# expansion_module_dual_rotary_encoder.net
KiCad netlist of a schematic drawn in EAGLE
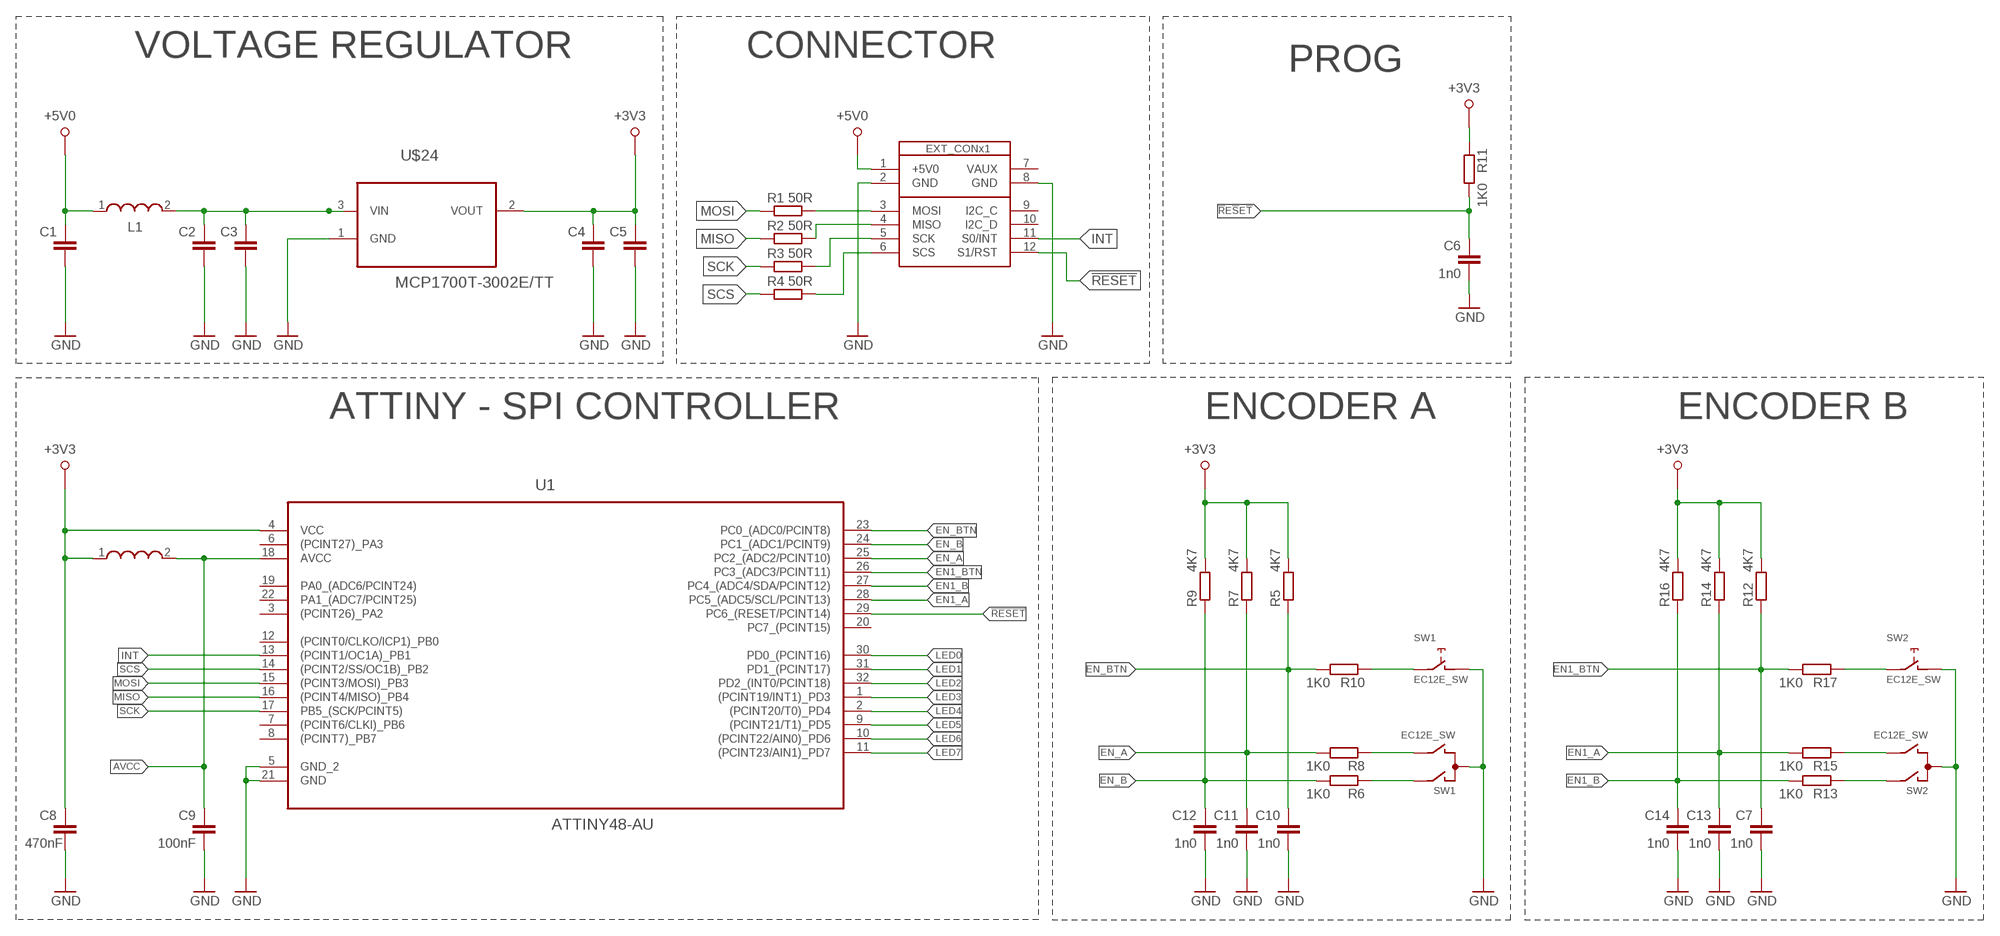
[diagram p0: schematic, sheet 1]

(export (version "E")
  (design (tool "Eeschema 10.0.6"))
  (components
    (comp (ref "C1")
      (value "C-EUC0805")
      (footprint "eagle-import:C0805")
      (libsource (lib "eagle-import") (part "C-EUC0805"))
    )
    (comp (ref "C2")
      (value "C-EUC0805")
      (footprint "eagle-import:C0805")
      (libsource (lib "eagle-import") (part "C-EUC0805"))
    )
    (comp (ref "C3")
      (value "C-EUC0805")
      (footprint "eagle-import:C0805")
      (libsource (lib "eagle-import") (part "C-EUC0805"))
    )
    (comp (ref "C4")
      (value "C-EUC0805")
      (footprint "eagle-import:C0805")
      (libsource (lib "eagle-import") (part "C-EUC0805"))
    )
    (comp (ref "C5")
      (value "C-EUC0805")
      (footprint "eagle-import:C0805")
      (libsource (lib "eagle-import") (part "C-EUC0805"))
    )
    (comp (ref "C6")
      (value "1n0")
      (footprint "eagle-import:C0805")
      (libsource (lib "eagle-import") (part "C-EUC0805"))
    )
    (comp (ref "C7")
      (value "1n0")
      (footprint "eagle-import:C0805")
      (libsource (lib "eagle-import") (part "C-EUC0805"))
    )
    (comp (ref "C8")
      (value "470nF")
      (footprint "eagle-import:C0805")
      (libsource (lib "eagle-import") (part "C-EUC0805"))
    )
    (comp (ref "C9")
      (value "100nF")
      (footprint "eagle-import:C0805")
      (libsource (lib "eagle-import") (part "C-EUC0805"))
    )
    (comp (ref "C10")
      (value "1n0")
      (footprint "eagle-import:C0805")
      (libsource (lib "eagle-import") (part "C-EUC0805"))
    )
    (comp (ref "C11")
      (value "1n0")
      (footprint "eagle-import:C0805")
      (libsource (lib "eagle-import") (part "C-EUC0805"))
    )
    (comp (ref "C12")
      (value "1n0")
      (footprint "eagle-import:C0805")
      (libsource (lib "eagle-import") (part "C-EUC0805"))
    )
    (comp (ref "C13")
      (value "1n0")
      (footprint "eagle-import:C0805")
      (libsource (lib "eagle-import") (part "C-EUC0805"))
    )
    (comp (ref "C14")
      (value "1n0")
      (footprint "eagle-import:C0805")
      (libsource (lib "eagle-import") (part "C-EUC0805"))
    )
    (comp (ref "L1")
      (value "WE-LQ_1210")
      (footprint "eagle-import:WE-LQ_M")
      (libsource (lib "eagle-import") (part "WE-LQ_1210"))
    )
    (comp (ref "L2")
      (value "WE-PMI_0805")
      (footprint "eagle-import:WE-PMI_0805")
      (libsource (lib "eagle-import") (part "WE-PMI_0805"))
    )
    (comp (ref "R1")
      (value "50R")
      (footprint "eagle-import:R0805")
      (libsource (lib "eagle-import") (part "R-EU_R0805"))
    )
    (comp (ref "R2")
      (value "50R")
      (footprint "eagle-import:R0805")
      (libsource (lib "eagle-import") (part "R-EU_R0805"))
    )
    (comp (ref "R3")
      (value "50R")
      (footprint "eagle-import:R0805")
      (libsource (lib "eagle-import") (part "R-EU_R0805"))
    )
    (comp (ref "R4")
      (value "50R")
      (footprint "eagle-import:R0805")
      (libsource (lib "eagle-import") (part "R-EU_R0805"))
    )
    (comp (ref "R5")
      (value "4K7")
      (footprint "eagle-import:R0805")
      (libsource (lib "eagle-import") (part "R-EU_R0805"))
    )
    (comp (ref "R6")
      (value "1K0")
      (footprint "eagle-import:R0805")
      (libsource (lib "eagle-import") (part "R-EU_R0805"))
    )
    (comp (ref "R7")
      (value "4K7")
      (footprint "eagle-import:R0805")
      (libsource (lib "eagle-import") (part "R-EU_R0805"))
    )
    (comp (ref "R8")
      (value "1K0")
      (footprint "eagle-import:R0805")
      (libsource (lib "eagle-import") (part "R-EU_R0805"))
    )
    (comp (ref "R9")
      (value "4K7")
      (footprint "eagle-import:R0805")
      (libsource (lib "eagle-import") (part "R-EU_R0805"))
    )
    (comp (ref "R10")
      (value "1K0")
      (footprint "eagle-import:R0805")
      (libsource (lib "eagle-import") (part "R-EU_R0805"))
    )
    (comp (ref "R11")
      (value "1K0")
      (footprint "eagle-import:R0805")
      (libsource (lib "eagle-import") (part "R-EU_R0805"))
    )
    (comp (ref "R12")
      (value "4K7")
      (footprint "eagle-import:R0805")
      (libsource (lib "eagle-import") (part "R-EU_R0805"))
    )
    (comp (ref "R13")
      (value "1K0")
      (footprint "eagle-import:R0805")
      (libsource (lib "eagle-import") (part "R-EU_R0805"))
    )
    (comp (ref "R14")
      (value "4K7")
      (footprint "eagle-import:R0805")
      (libsource (lib "eagle-import") (part "R-EU_R0805"))
    )
    (comp (ref "R15")
      (value "1K0")
      (footprint "eagle-import:R0805")
      (libsource (lib "eagle-import") (part "R-EU_R0805"))
    )
    (comp (ref "R16")
      (value "4K7")
      (footprint "eagle-import:R0805")
      (libsource (lib "eagle-import") (part "R-EU_R0805"))
    )
    (comp (ref "R17")
      (value "1K0")
      (footprint "eagle-import:R0805")
      (libsource (lib "eagle-import") (part "R-EU_R0805"))
    )
    (comp (ref "SW1")
      (value "EC12E_SW")
      (footprint "eagle-import:ALPS_EC12E_SW")
      (fields (field (name "MPN") "EC12E2424407"))
      (libsource (lib "eagle-import") (part "EC12E_SW"))
    )
    (comp (ref "SW2")
      (value "EC12E_SW")
      (footprint "eagle-import:ALPS_EC12E_SW")
      (fields (field (name "MPN") "EC12E2424407"))
      (libsource (lib "eagle-import") (part "EC12E_SW"))
    )
    (comp (ref "U$1")
      (value "SB_EXT_CON_X1_SPI")
      (footprint "eagle-import:SB_EXT_CON_X1_FULL")
      (libsource (lib "eagle-import") (part "SB_EXT_CON_X1_SPI"))
    )
    (comp (ref "U$24")
      (value "MCP1700T-3002E/TT")
      (footprint "eagle-import:SOT95P237X112-3N")
      (libsource (lib "eagle-import") (part "MCP1700T-3002E/TT"))
    )
    (comp (ref "U1")
      (value "ATTINY48-AU")
      (footprint "eagle-import:QFP80P900X900X120-32N")
      (libsource (lib "eagle-import") (part "ATTINY48-AU"))
    )
  )
  (nets
    (net (code "1") (name "+3V3") (class "Default")
      (node (ref "C4") (pin "2") (pinfunction "2_2") (pintype "passive"))
      (node (ref "C5") (pin "2") (pinfunction "2_2") (pintype "passive"))
      (node (ref "C8") (pin "2") (pinfunction "2_2") (pintype "passive"))
      (node (ref "L2") (pin "1") (pinfunction "1_1") (pintype "passive"))
      (node (ref "R11") (pin "1") (pinfunction "1_1") (pintype "passive"))
      (node (ref "R12") (pin "2") (pinfunction "2_2") (pintype "passive"))
      (node (ref "R14") (pin "2") (pinfunction "2_2") (pintype "passive"))
      (node (ref "R16") (pin "2") (pinfunction "2_2") (pintype "passive"))
      (node (ref "R5") (pin "2") (pinfunction "2_2") (pintype "passive"))
      (node (ref "R7") (pin "2") (pinfunction "2_2") (pintype "passive"))
      (node (ref "R9") (pin "2") (pinfunction "2_2") (pintype "passive"))
      (node (ref "U$24") (pin "2") (pinfunction "VOUT_2") (pintype "output"))
      (node (ref "U1") (pin "4") (pinfunction "VCC_4") (pintype "power_in"))
    )
    (net (code "2") (name "+5V0") (class "Default")
      (node (ref "C1") (pin "2") (pinfunction "2_2") (pintype "passive"))
      (node (ref "L1") (pin "1") (pinfunction "1_1") (pintype "passive"))
      (node (ref "U$1") (pin "1") (pinfunction "+5V0_1") (pintype "bidirectional"))
    )
    (net (code "3") (name "/~{RESET}") (class "Default")
      (node (ref "U$1") (pin "12") (pinfunction "S1/RST_12") (pintype "bidirectional"))
      (node (ref "U1") (pin "29") (pinfunction "PC6_(RESET/PCINT14)_29") (pintype "bidirectional"))
    )
    (net (code "4") (name "/~{R}E~{S}E~{T}") (class "Default")
      (node (ref "C6") (pin "2") (pinfunction "2_2") (pintype "passive"))
      (node (ref "R11") (pin "2") (pinfunction "2_2") (pintype "passive"))
    )
    (net (code "5") (name "AVCC") (class "Default")
      (node (ref "C9") (pin "2") (pinfunction "2_2") (pintype "passive"))
      (node (ref "L2") (pin "2") (pinfunction "2_2") (pintype "passive"))
      (node (ref "U1") (pin "18") (pinfunction "AVCC_18") (pintype "power_in"))
    )
    (net (code "6") (name "EN1_A") (class "Default")
      (node (ref "C13") (pin "2") (pinfunction "2_2") (pintype "passive"))
      (node (ref "R14") (pin "1") (pinfunction "1_1") (pintype "passive"))
      (node (ref "R15") (pin "2") (pinfunction "2_2") (pintype "passive"))
      (node (ref "U1") (pin "28") (pinfunction "PC5_(ADC5/SCL/PCINT13)_28") (pintype "bidirectional"))
    )
    (net (code "7") (name "EN1_B") (class "Default")
      (node (ref "C14") (pin "2") (pinfunction "2_2") (pintype "passive"))
      (node (ref "R13") (pin "2") (pinfunction "2_2") (pintype "passive"))
      (node (ref "R16") (pin "1") (pinfunction "1_1") (pintype "passive"))
      (node (ref "U1") (pin "27") (pinfunction "PC4_(ADC4/SDA/PCINT12)_27") (pintype "bidirectional"))
    )
    (net (code "8") (name "EN1_BTN") (class "Default")
      (node (ref "C7") (pin "2") (pinfunction "2_2") (pintype "passive"))
      (node (ref "R12") (pin "1") (pinfunction "1_1") (pintype "passive"))
      (node (ref "R17") (pin "2") (pinfunction "2_2") (pintype "passive"))
      (node (ref "U1") (pin "26") (pinfunction "PC3_(ADC3/PCINT11)_26") (pintype "bidirectional"))
    )
    (net (code "9") (name "EN_A") (class "Default")
      (node (ref "C11") (pin "2") (pinfunction "2_2") (pintype "passive"))
      (node (ref "R7") (pin "1") (pinfunction "1_1") (pintype "passive"))
      (node (ref "R8") (pin "2") (pinfunction "2_2") (pintype "passive"))
      (node (ref "U1") (pin "25") (pinfunction "PC2_(ADC2/PCINT10)_25") (pintype "bidirectional"))
    )
    (net (code "10") (name "EN_B") (class "Default")
      (node (ref "C12") (pin "2") (pinfunction "2_2") (pintype "passive"))
      (node (ref "R6") (pin "2") (pinfunction "2_2") (pintype "passive"))
      (node (ref "R9") (pin "1") (pinfunction "1_1") (pintype "passive"))
      (node (ref "U1") (pin "24") (pinfunction "PC1_(ADC1/PCINT9)_24") (pintype "bidirectional"))
    )
    (net (code "11") (name "EN_BTN") (class "Default")
      (node (ref "C10") (pin "2") (pinfunction "2_2") (pintype "passive"))
      (node (ref "R10") (pin "2") (pinfunction "2_2") (pintype "passive"))
      (node (ref "R5") (pin "1") (pinfunction "1_1") (pintype "passive"))
      (node (ref "U1") (pin "23") (pinfunction "PC0_(ADC0/PCINT8)_23") (pintype "bidirectional"))
    )
    (net (code "12") (name "GND") (class "Default")
      (node (ref "C1") (pin "1") (pinfunction "1_1") (pintype "passive"))
      (node (ref "C10") (pin "1") (pinfunction "1_1") (pintype "passive"))
      (node (ref "C11") (pin "1") (pinfunction "1_1") (pintype "passive"))
      (node (ref "C12") (pin "1") (pinfunction "1_1") (pintype "passive"))
      (node (ref "C13") (pin "1") (pinfunction "1_1") (pintype "passive"))
      (node (ref "C14") (pin "1") (pinfunction "1_1") (pintype "passive"))
      (node (ref "C2") (pin "1") (pinfunction "1_1") (pintype "passive"))
      (node (ref "C3") (pin "1") (pinfunction "1_1") (pintype "passive"))
      (node (ref "C4") (pin "1") (pinfunction "1_1") (pintype "passive"))
      (node (ref "C5") (pin "1") (pinfunction "1_1") (pintype "passive"))
      (node (ref "C6") (pin "1") (pinfunction "1_1") (pintype "passive"))
      (node (ref "C7") (pin "1") (pinfunction "1_1") (pintype "passive"))
      (node (ref "C8") (pin "1") (pinfunction "1_1") (pintype "passive"))
      (node (ref "C9") (pin "1") (pinfunction "1_1") (pintype "passive"))
      (node (ref "SW1") (pin "C") (pinfunction "C_C") (pintype "passive"))
      (node (ref "SW1") (pin "D") (pinfunction "1_D") (pintype "passive"))
      (node (ref "SW2") (pin "C") (pinfunction "C_C") (pintype "passive"))
      (node (ref "SW2") (pin "D") (pinfunction "1_D") (pintype "passive"))
      (node (ref "U$1") (pin "2") (pinfunction "GND_2") (pintype "bidirectional"))
      (node (ref "U$1") (pin "8") (pinfunction "GND_8") (pintype "bidirectional"))
      (node (ref "U$24") (pin "1") (pinfunction "GND_1") (pintype "passive"))
      (node (ref "U1") (pin "21") (pinfunction "GND_21") (pintype "passive"))
      (node (ref "U1") (pin "5") (pinfunction "GND_2_5") (pintype "passive"))
    )
    (net (code "13") (name "INT") (class "Default")
      (node (ref "U$1") (pin "11") (pinfunction "S0/INT_11") (pintype "bidirectional"))
      (node (ref "U1") (pin "13") (pinfunction "(PCINT1/OC1A)_PB1_13") (pintype "bidirectional"))
    )
    (net (code "14") (name "LED0") (class "Default")
      (node (ref "U1") (pin "30") (pinfunction "PD0_(PCINT16)_30") (pintype "bidirectional"))
    )
    (net (code "15") (name "LED1") (class "Default")
      (node (ref "U1") (pin "31") (pinfunction "PD1_(PCINT17)_31") (pintype "bidirectional"))
    )
    (net (code "16") (name "LED2") (class "Default")
      (node (ref "U1") (pin "32") (pinfunction "PD2_(INT0/PCINT18)_32") (pintype "bidirectional"))
    )
    (net (code "17") (name "LED3") (class "Default")
      (node (ref "U1") (pin "1") (pinfunction "(PCINT19/INT1)_PD3_1") (pintype "bidirectional"))
    )
    (net (code "18") (name "LED4") (class "Default")
      (node (ref "U1") (pin "2") (pinfunction "(PCINT20/T0)_PD4_2") (pintype "bidirectional"))
    )
    (net (code "19") (name "LED5") (class "Default")
      (node (ref "U1") (pin "9") (pinfunction "(PCINT21/T1)_PD5_9") (pintype "bidirectional"))
    )
    (net (code "20") (name "LED6") (class "Default")
      (node (ref "U1") (pin "10") (pinfunction "(PCINT22/AIN0)_PD6_10") (pintype "bidirectional"))
    )
    (net (code "21") (name "LED7") (class "Default")
      (node (ref "U1") (pin "11") (pinfunction "(PCINT23/AIN1)_PD7_11") (pintype "bidirectional"))
    )
    (net (code "22") (name "MISO") (class "Default")
      (node (ref "R2") (pin "1") (pinfunction "1_1") (pintype "passive"))
      (node (ref "U1") (pin "16") (pinfunction "(PCINT4/MISO)_PB4_16") (pintype "bidirectional"))
    )
    (net (code "23") (name "MOSI") (class "Default")
      (node (ref "R1") (pin "1") (pinfunction "1_1") (pintype "passive"))
      (node (ref "U1") (pin "15") (pinfunction "(PCINT3/MOSI)_PB3_15") (pintype "bidirectional"))
    )
    (net (code "24") (name "Net-(R6-Pad1)") (class "Default")
      (node (ref "R6") (pin "1") (pinfunction "1_1") (pintype "passive"))
      (node (ref "SW1") (pin "A") (pinfunction "A_A") (pintype "passive"))
    )
    (net (code "25") (name "Net-(R8-Pad1)") (class "Default")
      (node (ref "R8") (pin "1") (pinfunction "1_1") (pintype "passive"))
      (node (ref "SW1") (pin "B") (pinfunction "B_B") (pintype "passive"))
    )
    (net (code "26") (name "Net-(R13-Pad1)") (class "Default")
      (node (ref "R13") (pin "1") (pinfunction "1_1") (pintype "passive"))
      (node (ref "SW2") (pin "A") (pinfunction "A_A") (pintype "passive"))
    )
    (net (code "27") (name "Net-(R15-Pad1)") (class "Default")
      (node (ref "R15") (pin "1") (pinfunction "1_1") (pintype "passive"))
      (node (ref "SW2") (pin "B") (pinfunction "B_B") (pintype "passive"))
    )
    (net (code "28") (name "Net-(SW1B-2)") (class "Default")
      (node (ref "R10") (pin "1") (pinfunction "1_1") (pintype "passive"))
      (node (ref "SW1") (pin "E") (pinfunction "2_E") (pintype "passive"))
    )
    (net (code "29") (name "Net-(SW2B-2)") (class "Default")
      (node (ref "R17") (pin "1") (pinfunction "1_1") (pintype "passive"))
      (node (ref "SW2") (pin "E") (pinfunction "2_E") (pintype "passive"))
    )
    (net (code "30") (name "Net-(U$1-MISO)") (class "Default")
      (node (ref "R2") (pin "2") (pinfunction "2_2") (pintype "passive"))
      (node (ref "U$1") (pin "4") (pinfunction "MISO_4") (pintype "bidirectional"))
    )
    (net (code "31") (name "Net-(U$1-MOSI)") (class "Default")
      (node (ref "R1") (pin "2") (pinfunction "2_2") (pintype "passive"))
      (node (ref "U$1") (pin "3") (pinfunction "MOSI_3") (pintype "bidirectional"))
    )
    (net (code "32") (name "Net-(U$1-SCK)") (class "Default")
      (node (ref "R3") (pin "2") (pinfunction "2_2") (pintype "passive"))
      (node (ref "U$1") (pin "5") (pinfunction "SCK_5") (pintype "bidirectional"))
    )
    (net (code "33") (name "Net-(U$1-SCS)") (class "Default")
      (node (ref "R4") (pin "2") (pinfunction "2_2") (pintype "passive"))
      (node (ref "U$1") (pin "6") (pinfunction "SCS_6") (pintype "bidirectional"))
    )
    (net (code "34") (name "Net-(U$24-VIN)") (class "Default")
      (node (ref "C2") (pin "2") (pinfunction "2_2") (pintype "passive"))
      (node (ref "C3") (pin "2") (pinfunction "2_2") (pintype "passive"))
      (node (ref "L1") (pin "2") (pinfunction "2_2") (pintype "passive"))
      (node (ref "U$24") (pin "3") (pinfunction "VIN_3") (pintype "input"))
    )
    (net (code "35") (name "SCK") (class "Default")
      (node (ref "R3") (pin "1") (pinfunction "1_1") (pintype "passive"))
      (node (ref "U1") (pin "17") (pinfunction "PB5_(SCK/PCINT5)_17") (pintype "bidirectional"))
    )
    (net (code "36") (name "SCS") (class "Default")
      (node (ref "R4") (pin "1") (pinfunction "1_1") (pintype "passive"))
      (node (ref "U1") (pin "14") (pinfunction "(PCINT2/SS/OC1B)_PB2_14") (pintype "bidirectional"))
    )
    (net (code "37") (name "unconnected-(U$1-I2C_C-Pad9)") (class "Default")
      (node (ref "U$1") (pin "9") (pinfunction "I2C_C_9") (pintype "bidirectional"))
    )
    (net (code "38") (name "unconnected-(U$1-I2C_D-Pad10)") (class "Default")
      (node (ref "U$1") (pin "10") (pinfunction "I2C_D_10") (pintype "bidirectional"))
    )
    (net (code "39") (name "unconnected-(U$1-VAUX-Pad7)") (class "Default")
      (node (ref "U$1") (pin "7") (pinfunction "VAUX_7") (pintype "bidirectional"))
    )
    (net (code "40") (name "unconnected-(U1-(PCINT0{slash}CLKO{slash}ICP1)_PB0-Pad12)") (class "Default")
      (node (ref "U1") (pin "12") (pinfunction "(PCINT0/CLKO/ICP1)_PB0_12") (pintype "bidirectional"))
    )
    (net (code "41") (name "unconnected-(U1-(PCINT6{slash}CLKI)_PB6-Pad7)") (class "Default")
      (node (ref "U1") (pin "7") (pinfunction "(PCINT6/CLKI)_PB6_7") (pintype "bidirectional"))
    )
    (net (code "42") (name "unconnected-(U1-(PCINT7)_PB7-Pad8)") (class "Default")
      (node (ref "U1") (pin "8") (pinfunction "(PCINT7)_PB7_8") (pintype "bidirectional"))
    )
    (net (code "43") (name "unconnected-(U1-(PCINT26)_PA2-Pad3)") (class "Default")
      (node (ref "U1") (pin "3") (pinfunction "(PCINT26)_PA2_3") (pintype "bidirectional"))
    )
    (net (code "44") (name "unconnected-(U1-(PCINT27)_PA3-Pad6)") (class "Default")
      (node (ref "U1") (pin "6") (pinfunction "(PCINT27)_PA3_6") (pintype "bidirectional"))
    )
    (net (code "45") (name "unconnected-(U1-PA0_(ADC6{slash}PCINT24)-Pad19)") (class "Default")
      (node (ref "U1") (pin "19") (pinfunction "PA0_(ADC6/PCINT24)_19") (pintype "bidirectional"))
    )
    (net (code "46") (name "unconnected-(U1-PA1_(ADC7{slash}PCINT25)-Pad22)") (class "Default")
      (node (ref "U1") (pin "22") (pinfunction "PA1_(ADC7/PCINT25)_22") (pintype "bidirectional"))
    )
    (net (code "47") (name "unconnected-(U1-PC7_(PCINT15)-Pad20)") (class "Default")
      (node (ref "U1") (pin "20") (pinfunction "PC7_(PCINT15)_20") (pintype "bidirectional"))
    )
  )
)
